# ESP32_with_USBC.net
KiCad netlist of a schematic drawn in Altium Designer
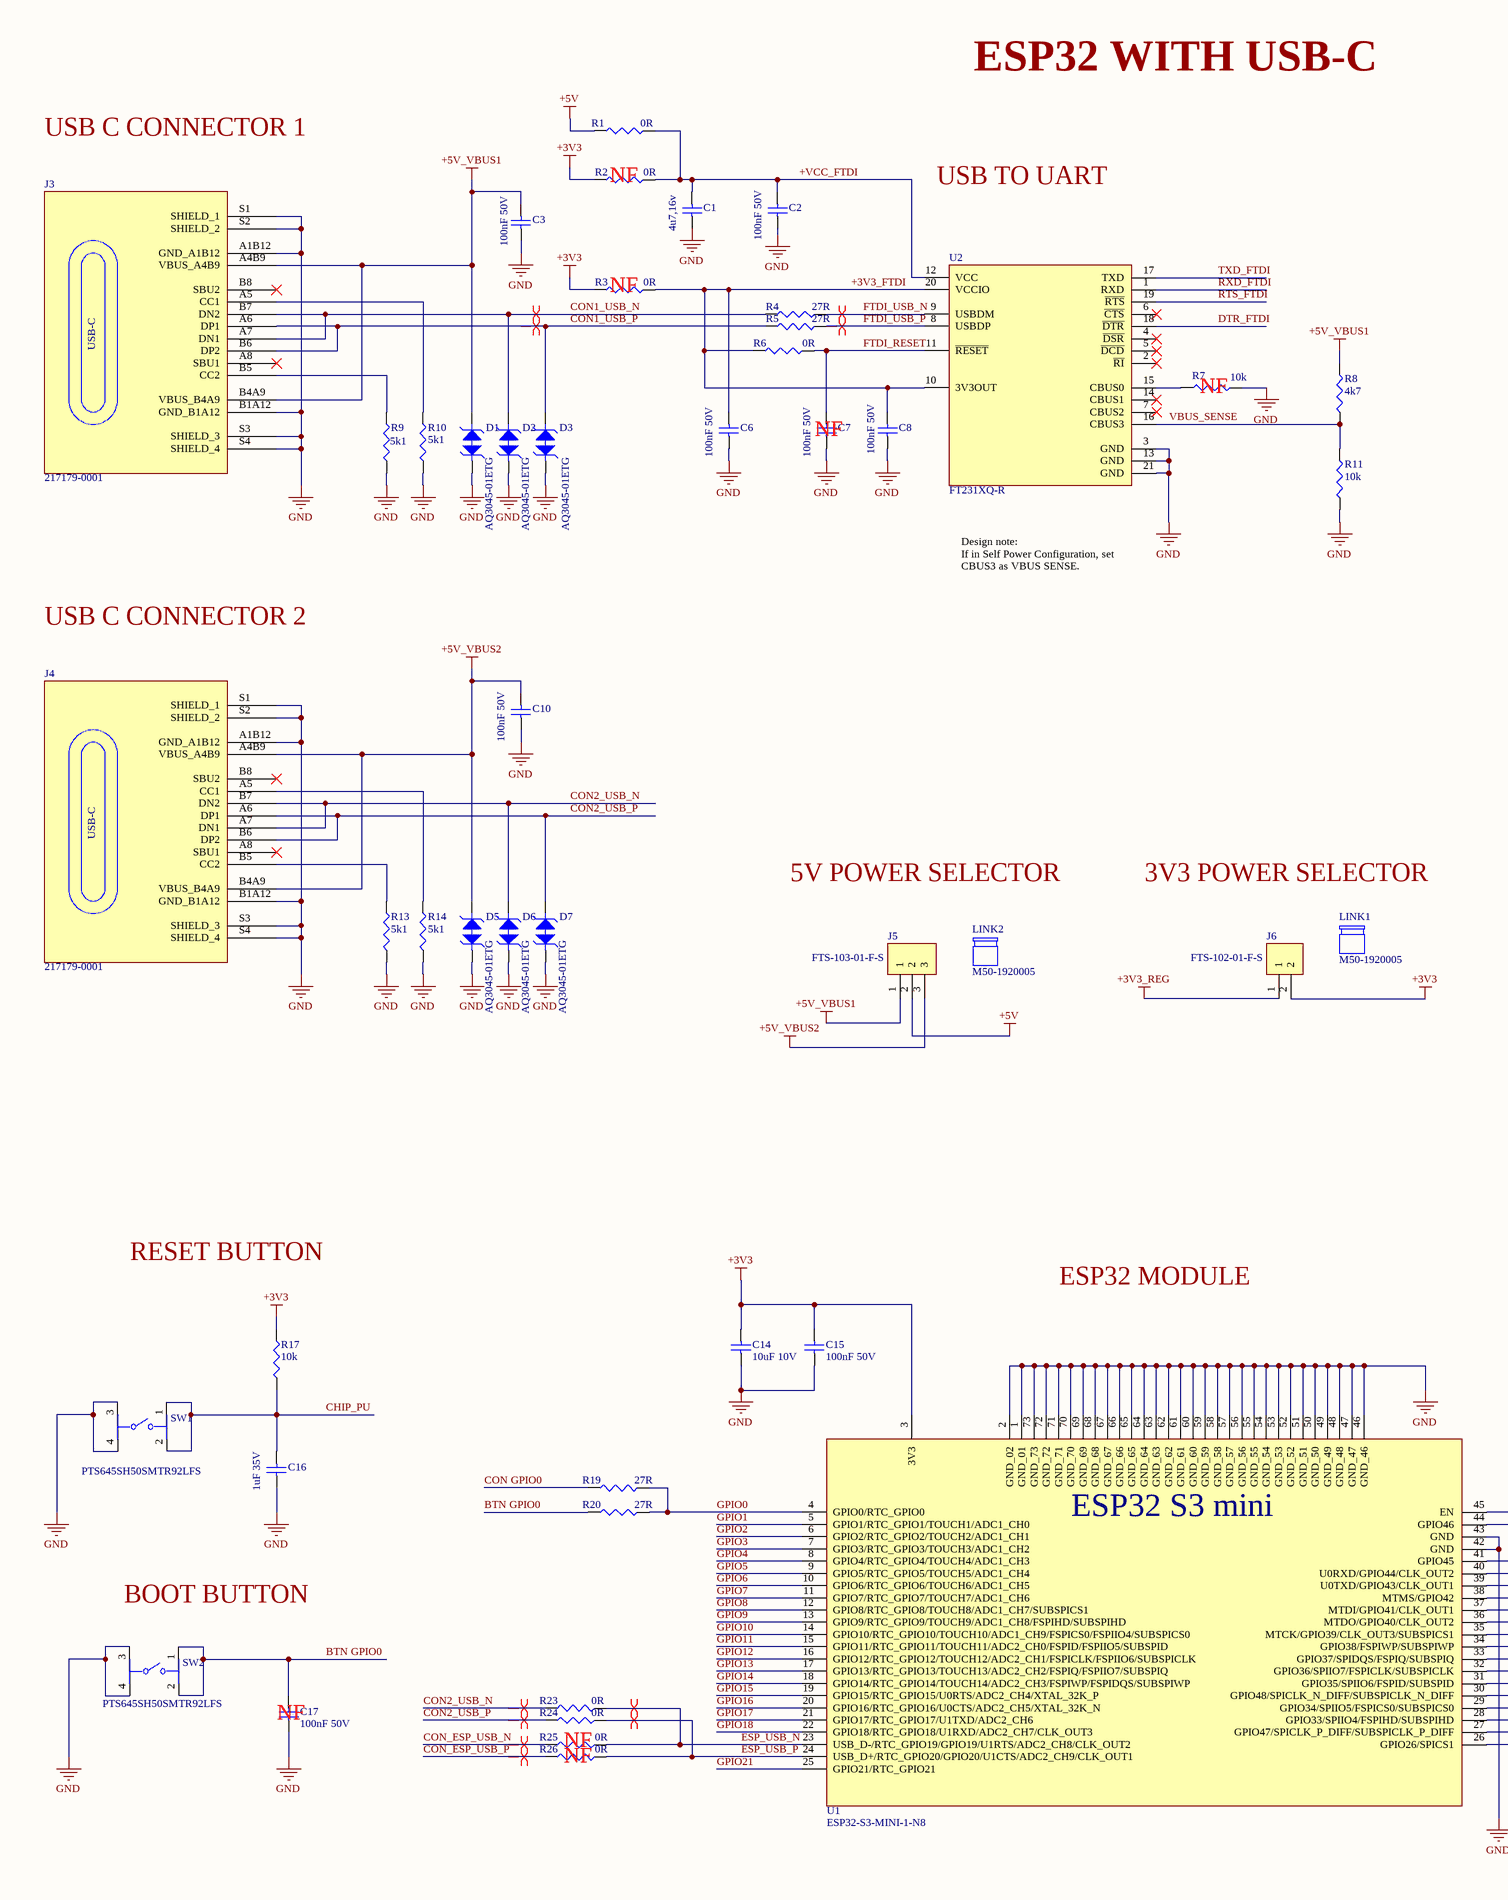
[diagram p0: ESP32 with USBC.SchDoc, left]
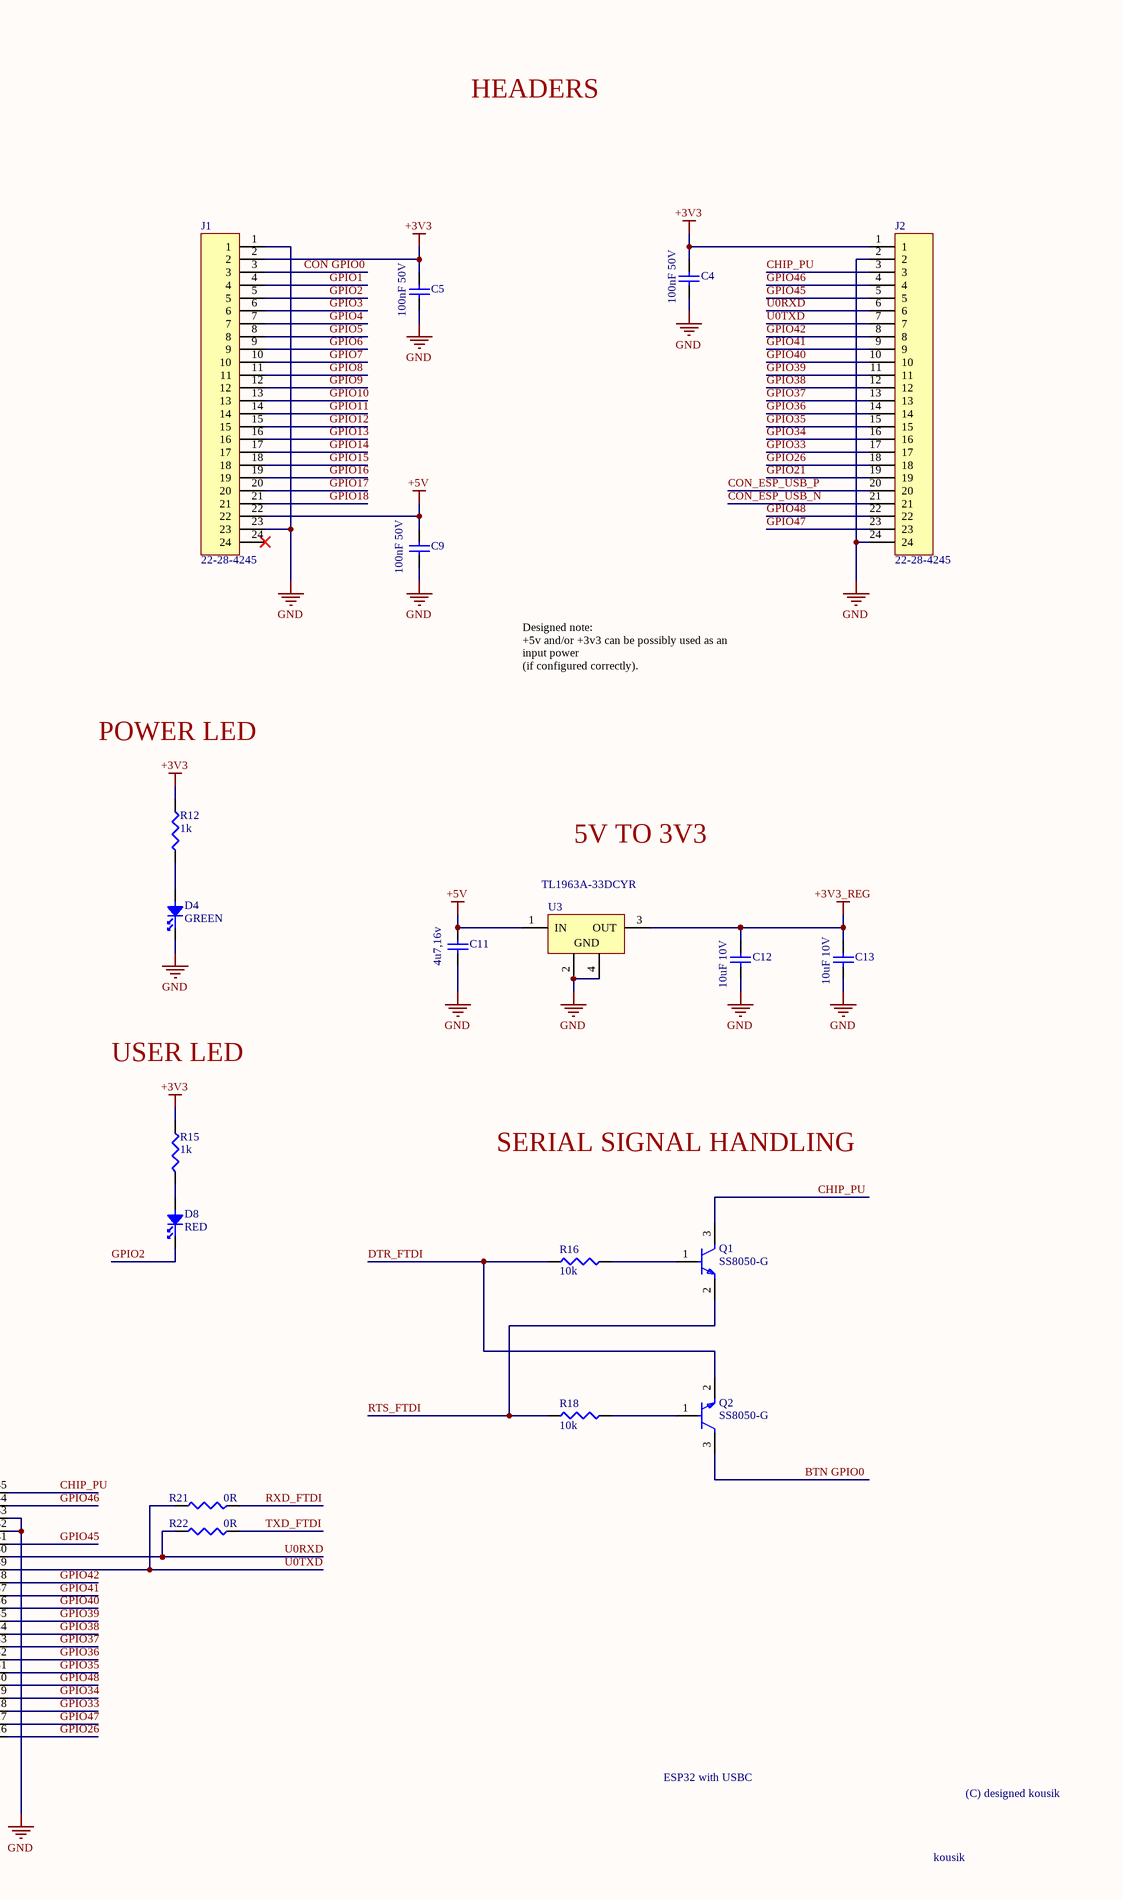
[diagram p1: ESP32 with USBC.SchDoc, right]

(export (version "E")
  (design (tool "Eeschema 10.0.6"))
  (components
    (comp (ref "C1")
      (value "4u7,16v")
      (footprint "CAPC1005X65N")
      (description "CAP CER 4.7UF 16V X5R 0402")
      (fields
        (field (name "MANUFACTURER") "Samsung Electro-Mechanics")
        (field (name "MANUFACTURER PART NUMBER") "CL05A475MO5NUNC")
      )
      (libsource (lib "Schlib") (part "CL05A475MO5NUNC"))
    )
    (comp (ref "C2")
      (value "100nF 50V")
      (footprint "CAPC1005X65N")
      (description "CAP CER 0.1UF 50V X7R 0402")
      (fields
        (field (name "MANUFACTURER") "Samsung Electro-Mechanics")
        (field (name "MANUFACTURER PART NUMBER") "CL05B104KB54PNC")
      )
      (libsource (lib "Schlib") (part "CL05B104KB54PNC"))
    )
    (comp (ref "C3")
      (value "100nF 50V")
      (footprint "CAPC1005X65N")
      (description "CAP CER 0.1UF 50V X7R 0402")
      (fields
        (field (name "MANUFACTURER") "Samsung Electro-Mechanics")
        (field (name "MANUFACTURER PART NUMBER") "CL05B104KB54PNC")
      )
      (libsource (lib "Schlib") (part "CL05B104KB54PNC"))
    )
    (comp (ref "C4")
      (value "100nF 50V")
      (footprint "CAPC1005X65N")
      (description "CAP CER 0.1UF 50V X7R 0402")
      (fields
        (field (name "MANUFACTURER") "Samsung Electro-Mechanics")
        (field (name "MANUFACTURER PART NUMBER") "CL05B104KB54PNC")
      )
      (libsource (lib "Schlib") (part "CL05B104KB54PNC"))
    )
    (comp (ref "C5")
      (value "100nF 50V")
      (footprint "CAPC1005X65N")
      (description "CAP CER 0.1UF 50V X7R 0402")
      (fields
        (field (name "MANUFACTURER") "Samsung Electro-Mechanics")
        (field (name "MANUFACTURER PART NUMBER") "CL05B104KB54PNC")
      )
      (libsource (lib "Schlib") (part "CL05B104KB54PNC"))
    )
    (comp (ref "C6")
      (value "100nF 50V")
      (footprint "CAPC1005X65N")
      (description "CAP CER 0.1UF 50V X7R 0402")
      (fields
        (field (name "MANUFACTURER") "Samsung Electro-Mechanics")
        (field (name "MANUFACTURER PART NUMBER") "CL05B104KB54PNC")
      )
      (libsource (lib "Schlib") (part "CL05B104KB54PNC"))
    )
    (comp (ref "C7")
      (value "100nF 50V")
      (footprint "CAPC1005X65N")
      (description "CAP CER 0.1UF 50V X7R 0402")
      (fields
        (field (name "MANUFACTURER") "Samsung Electro-Mechanics")
        (field (name "MANUFACTURER PART NUMBER") "CL05B104KB54PNC")
      )
      (libsource (lib "Schlib") (part "CL05B104KB54PNC"))
    )
    (comp (ref "C8")
      (value "100nF 50V")
      (footprint "CAPC1005X65N")
      (description "CAP CER 0.1UF 50V X7R 0402")
      (fields
        (field (name "MANUFACTURER") "Samsung Electro-Mechanics")
        (field (name "MANUFACTURER PART NUMBER") "CL05B104KB54PNC")
      )
      (libsource (lib "Schlib") (part "CL05B104KB54PNC"))
    )
    (comp (ref "C9")
      (value "100nF 50V")
      (footprint "CAPC1005X65N")
      (description "CAP CER 0.1UF 50V X7R 0402")
      (fields
        (field (name "MANUFACTURER") "Samsung Electro-Mechanics")
        (field (name "MANUFACTURER PART NUMBER") "CL05B104KB54PNC")
      )
      (libsource (lib "Schlib") (part "CL05B104KB54PNC"))
    )
    (comp (ref "C10")
      (value "100nF 50V")
      (footprint "CAPC1005X65N")
      (description "CAP CER 0.1UF 50V X7R 0402")
      (fields
        (field (name "MANUFACTURER") "Samsung Electro-Mechanics")
        (field (name "MANUFACTURER PART NUMBER") "CL05B104KB54PNC")
      )
      (libsource (lib "Schlib") (part "CL05B104KB54PNC"))
    )
    (comp (ref "C11")
      (value "4u7,16v")
      (footprint "CAPC1005X65N")
      (description "CAP CER 4.7UF 16V X5R 0402")
      (fields
        (field (name "MANUFACTURER") "Samsung Electro-Mechanics")
        (field (name "MANUFACTURER PART NUMBER") "CL05A475MO5NUNC")
      )
      (libsource (lib "Schlib") (part "CL05A475MO5NUNC"))
    )
    (comp (ref "C12")
      (value "10uF 10V")
      (footprint "CAPC1005X65N")
      (description "CAP CER 10UF 10V X5R 0402")
      (fields
        (field (name "MANUFACTURER") "Samsung Electro-Mechanics")
        (field (name "MANUFACTURER PART NUMBER") "CL05A106MP8NUB8")
      )
      (libsource (lib "Schlib") (part "CL05A106MP8NUB8"))
    )
    (comp (ref "C13")
      (value "10uF 10V")
      (footprint "CAPC1005X65N")
      (description "CAP CER 10UF 10V X5R 0402")
      (fields
        (field (name "MANUFACTURER") "Samsung Electro-Mechanics")
        (field (name "MANUFACTURER PART NUMBER") "CL05A106MP8NUB8")
      )
      (libsource (lib "Schlib") (part "CL05A106MP8NUB8"))
    )
    (comp (ref "C14")
      (value "10uF 10V")
      (footprint "CAPC1005X65N")
      (description "CAP CER 10UF 10V X5R 0402")
      (fields
        (field (name "MANUFACTURER") "Samsung Electro-Mechanics")
        (field (name "MANUFACTURER PART NUMBER") "CL05A106MP8NUB8")
      )
      (libsource (lib "Schlib") (part "CL05A106MP8NUB8"))
    )
    (comp (ref "C15")
      (value "100nF 50V")
      (footprint "CAPC1005X65N")
      (description "CAP CER 0.1UF 50V X7R 0402")
      (fields
        (field (name "MANUFACTURER") "Samsung Electro-Mechanics")
        (field (name "MANUFACTURER PART NUMBER") "CL05B104KB54PNC")
      )
      (libsource (lib "Schlib") (part "CL05B104KB54PNC"))
    )
    (comp (ref "C16")
      (value "1uF 35V")
      (footprint "CAPC1005X65N")
      (description "CAP CER 1UF 35V X5R 0402")
      (fields
        (field (name "MANUFACTURER") "Samsung Electro-Mechanics")
        (field (name "MANUFACTURER PART NUMBER") "CL05A105KL5NRNC")
      )
      (libsource (lib "Schlib") (part "CL05A105KL5NRNC"))
    )
    (comp (ref "C17")
      (value "100nF 50V")
      (footprint "CAPC1005X65N")
      (description "CAP CER 0.1UF 50V X7R 0402")
      (fields
        (field (name "MANUFACTURER") "Samsung Electro-Mechanics")
        (field (name "MANUFACTURER PART NUMBER") "CL05B104KB54PNC")
      )
      (libsource (lib "Schlib") (part "CL05B104KB54PNC"))
    )
    (comp (ref "D1")
      (value "AQ3045-01ETG")
      (footprint "SOD882")
      (description "TVS DIODE 5.3VWM 12VC SOD882")
      (fields (field (name "MANUFACTURER") "Littelfuse") (field (name "LCSC PART NUMBER") "C3710326"))
      (libsource (lib "Schlib") (part "AQ3045-01ETG"))
    )
    (comp (ref "D2")
      (value "AQ3045-01ETG")
      (footprint "SOD882")
      (description "TVS DIODE 5.3VWM 12VC SOD882")
      (fields (field (name "MANUFACTURER") "Littelfuse") (field (name "LCSC PART NUMBER") "C3710326"))
      (libsource (lib "Schlib") (part "AQ3045-01ETG"))
    )
    (comp (ref "D3")
      (value "AQ3045-01ETG")
      (footprint "SOD882")
      (description "TVS DIODE 5.3VWM 12VC SOD882")
      (fields (field (name "MANUFACTURER") "Littelfuse") (field (name "LCSC PART NUMBER") "C3710326"))
      (libsource (lib "Schlib") (part "AQ3045-01ETG"))
    )
    (comp (ref "D4")
      (value "GREEN")
      (footprint "LED0402G")
      (description "LED YLW-GRN 0402 SMD")
      (fields
        (field (name "MANUFACTURER") "Vishay")
        (field (name "MANUFACTURER PART NUMBER") "VLMG1500-GS08")
      )
      (libsource (lib "Schlib") (part "VLMG1500-GS08"))
    )
    (comp (ref "D5")
      (value "AQ3045-01ETG")
      (footprint "SOD882")
      (description "TVS DIODE 5.3VWM 12VC SOD882")
      (fields (field (name "MANUFACTURER") "Littelfuse") (field (name "LCSC PART NUMBER") "C3710326"))
      (libsource (lib "Schlib") (part "AQ3045-01ETG"))
    )
    (comp (ref "D6")
      (value "AQ3045-01ETG")
      (footprint "SOD882")
      (description "TVS DIODE 5.3VWM 12VC SOD882")
      (fields (field (name "MANUFACTURER") "Littelfuse") (field (name "LCSC PART NUMBER") "C3710326"))
      (libsource (lib "Schlib") (part "AQ3045-01ETG"))
    )
    (comp (ref "D7")
      (value "AQ3045-01ETG")
      (footprint "SOD882")
      (description "TVS DIODE 5.3VWM 12VC SOD882")
      (fields (field (name "MANUFACTURER") "Littelfuse") (field (name "LCSC PART NUMBER") "C3710326"))
      (libsource (lib "Schlib") (part "AQ3045-01ETG"))
    )
    (comp (ref "D8")
      (value "RED")
      (footprint "LED0402R")
      (description "LED RED 0402 SMD")
      (fields
        (field (name "MANUFACTURER") "Vishay")
        (field (name "MANUFACTURER PART NUMBER") "VLMS1500-GS08")
      )
      (libsource (lib "Schlib") (part "VLMS1500-GS08"))
    )
    (comp (ref "J1")
      (value "22-28-4245")
      (footprint "HDR_1X24_2.54MM")
      (description "CONN HEADER VERT 24POS 2.54MM")
      (fields (field (name "MANUFACTURER") "Molex") (field (name "LCSC PART NUMBER") "C7145888"))
      (libsource (lib "Schlib") (part "22-28-4245"))
    )
    (comp (ref "J2")
      (value "22-28-4245")
      (footprint "HDR_1X24_2.54MM")
      (description "CONN HEADER VERT 24POS 2.54MM")
      (fields (field (name "MANUFACTURER") "Molex") (field (name "LCSC PART NUMBER") "C7145888"))
      (libsource (lib "") (part "22-28-4245_1"))
    )
    (comp (ref "J3")
      (value "217179-0001")
      (footprint "FP-2171790001-MFG")
      (description "CONN RCP USB2.0 TYP C 24P SMD RA")
      (fields (field (name "MANUFACTURER") "Molex") (field (name "LCSC PART NUMBER") "C3197684"))
      (libsource (lib "Schlib") (part "217179-0001"))
    )
    (comp (ref "J4")
      (value "217179-0001")
      (footprint "FP-2171790001-MFG")
      (description "CONN RCP USB2.0 TYP C 24P SMD RA")
      (fields (field (name "MANUFACTURER") "Molex") (field (name "LCSC PART NUMBER") "C3197684"))
      (libsource (lib "Schlib") (part "217179-0001"))
    )
    (comp (ref "J5")
      (value "FTS-103-01-F-S")
      (footprint "HDR_1X3_1.27MM")
      (description "CONN HEADER VERT 3POS 1.27MM")
      (fields (field (name "MANUFACTURER") "Samtec") (field (name "LCSC PART NUMBER") "C3333578"))
      (libsource (lib "Schlib") (part "FTS-103-01-F-S"))
    )
    (comp (ref "J6")
      (value "FTS-102-01-F-S")
      (footprint "HDR_1X2_1.27MM")
      (description "CONN HEADER VERT 2POS 1.27MM")
      (fields (field (name "MANUFACTURER") "Samtec") (field (name "LCSC PART NUMBER") "C6045317"))
      (libsource (lib "Schlib") (part "FTS-102-01-F-S"))
    )
    (comp (ref "LINK1")
      (value "M50-1920005")
      (description "CONN SHUNT 1.27MM RED")
      (fields (field (name "MANUFACTURER") "Harwin") (field (name "LCSC PART NUMBER") "C6985646"))
      (libsource (lib "Schlib") (part "M50-1920005"))
    )
    (comp (ref "LINK2")
      (value "M50-1920005")
      (description "CONN SHUNT 1.27MM RED")
      (fields (field (name "MANUFACTURER") "Harwin") (field (name "LCSC PART NUMBER") "C6985646"))
      (libsource (lib "Schlib") (part "M50-1920005"))
    )
    (comp (ref "Q1")
      (value "SS8050-G")
      (footprint "FP-SS8050-G-IPC_B")
      (description "TRANS NPN 25V 1.5A SOT-23-3")
      (fields (field (name "MANUFACTURER") "Comchip") (field (name "LCSC PART NUMBER") "C164886"))
      (libsource (lib "Schlib") (part "SS8050-G"))
    )
    (comp (ref "Q2")
      (value "SS8050-G")
      (footprint "FP-SS8050-G-IPC_B")
      (description "TRANS NPN 25V 1.5A SOT-23-3")
      (fields (field (name "MANUFACTURER") "Comchip") (field (name "LCSC PART NUMBER") "C164886"))
      (libsource (lib "Schlib") (part "SS8050-G"))
    )
    (comp (ref "R1")
      (value "0R")
      (footprint "RESC1005X37N")
      (description "RES 0 OHM JUMPER 1/16W 0402")
      (fields
        (field (name "MANUFACTURER") "Yageo Group")
        (field (name "MANUFACTURER PART NUMBER") "RC0402JR-070RL")
      )
      (libsource (lib "Schlib") (part "RC0402JR-070RL"))
    )
    (comp (ref "R2")
      (value "0R")
      (footprint "RESC1005X37N")
      (description "RES 0 OHM JUMPER 1/16W 0402")
      (fields
        (field (name "MANUFACTURER") "Yageo Group")
        (field (name "MANUFACTURER PART NUMBER") "RC0402JR-070RL")
      )
      (libsource (lib "Schlib") (part "RC0402JR-070RL"))
    )
    (comp (ref "R3")
      (value "0R")
      (footprint "RESC1005X37N")
      (description "RES 0 OHM JUMPER 1/16W 0402")
      (fields
        (field (name "MANUFACTURER") "Yageo Group")
        (field (name "MANUFACTURER PART NUMBER") "RC0402JR-070RL")
      )
      (libsource (lib "Schlib") (part "RC0402JR-070RL"))
    )
    (comp (ref "R4")
      (value "27R")
      (footprint "RESC1005X37N")
      (description "RES 27 OHM 1% 1/16W 0402")
      (fields
        (field (name "MANUFACTURER") "Yageo Group")
        (field (name "MANUFACTURER PART NUMBER") "RC0402FR-0727RL")
      )
      (libsource (lib "Schlib") (part "RC0402FR-0727RL"))
    )
    (comp (ref "R5")
      (value "27R")
      (footprint "RESC1005X37N")
      (description "RES 27 OHM 1% 1/16W 0402")
      (fields
        (field (name "MANUFACTURER") "Yageo Group")
        (field (name "MANUFACTURER PART NUMBER") "RC0402FR-0727RL")
      )
      (libsource (lib "Schlib") (part "RC0402FR-0727RL"))
    )
    (comp (ref "R6")
      (value "0R")
      (footprint "RESC1005X37N")
      (description "RES 0 OHM JUMPER 1/16W 0402")
      (fields
        (field (name "MANUFACTURER") "Yageo Group")
        (field (name "MANUFACTURER PART NUMBER") "RC0402JR-070RL")
      )
      (libsource (lib "Schlib") (part "RC0402JR-070RL"))
    )
    (comp (ref "R7")
      (value "10k")
      (footprint "RESC1005X37N")
      (description "RES SMD 10K OHM 1% 1/16W 0402")
      (fields
        (field (name "MANUFACTURER") "Yageo Group")
        (field (name "MANUFACTURER PART NUMBER") "AC0402FR-0710KL")
      )
      (libsource (lib "Schlib") (part "AC0402FR-0710KL"))
    )
    (comp (ref "R8")
      (value "4k7")
      (footprint "RESC1005X37N")
      (description "RES 4.7K OHM 1% 1/16W 0402")
      (fields
        (field (name "MANUFACTURER") "Yageo Group")
        (field (name "MANUFACTURER PART NUMBER") "RC0402FR-074K7L")
      )
      (libsource (lib "Schlib") (part "RC0402FR-074K7L"))
    )
    (comp (ref "R9")
      (value "5k1")
      (footprint "RESC1005X37N")
      (description "RES SMD 5.1K OHM 1% 1/16W 0402")
      (fields
        (field (name "MANUFACTURER") "Yageo Group")
        (field (name "MANUFACTURER PART NUMBER") "AC0402FR-075K1L")
      )
      (libsource (lib "Schlib") (part "AC0402FR-075K1L"))
    )
    (comp (ref "R10")
      (value "5k1")
      (footprint "RESC1005X37N")
      (description "RES SMD 5.1K OHM 1% 1/16W 0402")
      (fields
        (field (name "MANUFACTURER") "Yageo Group")
        (field (name "MANUFACTURER PART NUMBER") "AC0402FR-075K1L")
      )
      (libsource (lib "Schlib") (part "AC0402FR-075K1L"))
    )
    (comp (ref "R11")
      (value "10k")
      (footprint "RESC1005X37N")
      (description "RES SMD 10K OHM 1% 1/16W 0402")
      (fields
        (field (name "MANUFACTURER") "Yageo Group")
        (field (name "MANUFACTURER PART NUMBER") "AC0402FR-0710KL")
      )
      (libsource (lib "Schlib") (part "AC0402FR-0710KL"))
    )
    (comp (ref "R12")
      (value "1k")
      (footprint "RESC1005X37N")
      (description "RES 1K OHM 1% 1/16W 0402")
      (fields
        (field (name "MANUFACTURER") "Yageo Group")
        (field (name "MANUFACTURER PART NUMBER") "RC0402FR-071KL")
      )
      (libsource (lib "Schlib") (part "RC0402FR-071KL"))
    )
    (comp (ref "R13")
      (value "5k1")
      (footprint "RESC1005X37N")
      (description "RES SMD 5.1K OHM 1% 1/16W 0402")
      (fields
        (field (name "MANUFACTURER") "Yageo Group")
        (field (name "MANUFACTURER PART NUMBER") "AC0402FR-075K1L")
      )
      (libsource (lib "Schlib") (part "AC0402FR-075K1L"))
    )
    (comp (ref "R14")
      (value "5k1")
      (footprint "RESC1005X37N")
      (description "RES SMD 5.1K OHM 1% 1/16W 0402")
      (fields
        (field (name "MANUFACTURER") "Yageo Group")
        (field (name "MANUFACTURER PART NUMBER") "AC0402FR-075K1L")
      )
      (libsource (lib "Schlib") (part "AC0402FR-075K1L"))
    )
    (comp (ref "R15")
      (value "1k")
      (footprint "RESC1005X37N")
      (description "RES 1K OHM 1% 1/16W 0402")
      (fields
        (field (name "MANUFACTURER") "Yageo Group")
        (field (name "MANUFACTURER PART NUMBER") "RC0402FR-071KL")
      )
      (libsource (lib "Schlib") (part "RC0402FR-071KL"))
    )
    (comp (ref "R16")
      (value "10k")
      (footprint "RESC1005X37N")
      (description "RES SMD 10K OHM 1% 1/16W 0402")
      (fields
        (field (name "MANUFACTURER") "Yageo Group")
        (field (name "MANUFACTURER PART NUMBER") "AC0402FR-0710KL")
      )
      (libsource (lib "Schlib") (part "AC0402FR-0710KL"))
    )
    (comp (ref "R17")
      (value "10k")
      (footprint "RESC1005X37N")
      (description "RES SMD 10K OHM 1% 1/16W 0402")
      (fields
        (field (name "MANUFACTURER") "Yageo Group")
        (field (name "MANUFACTURER PART NUMBER") "AC0402FR-0710KL")
      )
      (libsource (lib "Schlib") (part "AC0402FR-0710KL"))
    )
    (comp (ref "R18")
      (value "10k")
      (footprint "RESC1005X37N")
      (description "RES SMD 10K OHM 1% 1/16W 0402")
      (fields
        (field (name "MANUFACTURER") "Yageo Group")
        (field (name "MANUFACTURER PART NUMBER") "AC0402FR-0710KL")
      )
      (libsource (lib "Schlib") (part "AC0402FR-0710KL"))
    )
    (comp (ref "R19")
      (value "27R")
      (footprint "RESC1005X37N")
      (description "RES 27 OHM 1% 1/16W 0402")
      (fields
        (field (name "MANUFACTURER") "Yageo Group")
        (field (name "MANUFACTURER PART NUMBER") "RC0402FR-0727RL")
      )
      (libsource (lib "Schlib") (part "RC0402FR-0727RL"))
    )
    (comp (ref "R20")
      (value "27R")
      (footprint "RESC1005X37N")
      (description "RES 27 OHM 1% 1/16W 0402")
      (fields
        (field (name "MANUFACTURER") "Yageo Group")
        (field (name "MANUFACTURER PART NUMBER") "RC0402FR-0727RL")
      )
      (libsource (lib "Schlib") (part "RC0402FR-0727RL"))
    )
    (comp (ref "R21")
      (value "0R")
      (footprint "RESC1005X37N")
      (description "RES 0 OHM JUMPER 1/16W 0402")
      (fields
        (field (name "MANUFACTURER") "Yageo Group")
        (field (name "MANUFACTURER PART NUMBER") "RC0402JR-070RL")
      )
      (libsource (lib "Schlib") (part "RC0402JR-070RL"))
    )
    (comp (ref "R22")
      (value "0R")
      (footprint "RESC1005X37N")
      (description "RES 0 OHM JUMPER 1/16W 0402")
      (fields
        (field (name "MANUFACTURER") "Yageo Group")
        (field (name "MANUFACTURER PART NUMBER") "RC0402JR-070RL")
      )
      (libsource (lib "Schlib") (part "RC0402JR-070RL"))
    )
    (comp (ref "R23")
      (value "0R")
      (footprint "RESC1005X37N")
      (description "RES 0 OHM JUMPER 1/16W 0402")
      (fields
        (field (name "MANUFACTURER") "Yageo Group")
        (field (name "MANUFACTURER PART NUMBER") "RC0402JR-070RL")
      )
      (libsource (lib "Schlib") (part "RC0402JR-070RL"))
    )
    (comp (ref "R24")
      (value "0R")
      (footprint "RESC1005X37N")
      (description "RES 0 OHM JUMPER 1/16W 0402")
      (fields
        (field (name "MANUFACTURER") "Yageo Group")
        (field (name "MANUFACTURER PART NUMBER") "RC0402JR-070RL")
      )
      (libsource (lib "Schlib") (part "RC0402JR-070RL"))
    )
    (comp (ref "R25")
      (value "0R")
      (footprint "RESC1005X37N")
      (description "RES 0 OHM JUMPER 1/16W 0402")
      (fields
        (field (name "MANUFACTURER") "Yageo Group")
        (field (name "MANUFACTURER PART NUMBER") "RC0402JR-070RL")
      )
      (libsource (lib "Schlib") (part "RC0402JR-070RL"))
    )
    (comp (ref "R26")
      (value "0R")
      (footprint "RESC1005X37N")
      (description "RES 0 OHM JUMPER 1/16W 0402")
      (fields
        (field (name "MANUFACTURER") "Yageo Group")
        (field (name "MANUFACTURER PART NUMBER") "RC0402JR-070RL")
      )
      (libsource (lib "Schlib") (part "RC0402JR-070RL"))
    )
    (comp (ref "SW1")
      (value "PTS645SH50SMTR92LFS")
      (footprint "FP-PTS645SH50SMTR92LFS-MFG")
      (description "SWITCH TACTILE SPST-NO 0.05A 12V")
      (fields (field (name "MANUFACTURER") "C&K Components") (field (name "LCSC PART NUMBER") "C221869"))
      (libsource (lib "Schlib") (part "PTS645SH50SMTR92LFS"))
    )
    (comp (ref "SW2")
      (value "PTS645SH50SMTR92LFS")
      (footprint "FP-PTS645SH50SMTR92LFS-MFG")
      (description "SWITCH TACTILE SPST-NO 0.05A 12V")
      (fields (field (name "MANUFACTURER") "C&K Components") (field (name "LCSC PART NUMBER") "C221869"))
      (libsource (lib "Schlib") (part "PTS645SH50SMTR92LFS"))
    )
    (comp (ref "U1")
      (value "ESP32-S3-MINI-1-N8")
      (footprint "XCVR_ESP32-S3-MINI-1-N8")
      (description "20.5dBm ESP32-S3FN8 Chip 2.4GHz SMD WiFi Modules ROHS")
      (fields (field (name "MANUFACTURER") "Espressif Systems") (field (name "LCSC PART NUMBER") "C2913206"))
      (libsource (lib "Schlib") (part "ESP32-S3-MINI-1-N8"))
    )
    (comp (ref "U2")
      (value "FT231XQ-R")
      (footprint "FP-QFN-20-IPC_B")
      (description "IC USB SERIAL FULL UART 20QFN")
      (fields (field (name "MANUFACTURER") "FTDI") (field (name "LCSC PART NUMBER") "C132159"))
      (libsource (lib "Schlib") (part "FT231XQ-R"))
    )
    (comp (ref "U3")
      (value "TL1963A-33DCYR")
      (footprint "DCY0004A_N")
      (description "IC REG LIN 3.3V 1.5A SOT-223-4")
      (fields (field (name "MANUFACTURER") "Texas Instruments") (field (name "LCSC PART NUMBER") "C181262"))
      (libsource (lib "Schlib") (part "TL1963A-33DCYR"))
    )
  )
  (nets
    (net (code "1") (name "+3V3") (class "Default")
      (node (ref "C14") (pin "2") (pinfunction "2_2") (pintype "passive"))
      (node (ref "C15") (pin "2") (pinfunction "2_2") (pintype "passive"))
      (node (ref "C4") (pin "2") (pinfunction "2_2") (pintype "passive"))
      (node (ref "C5") (pin "2") (pinfunction "2_2") (pintype "passive"))
      (node (ref "J1") (pin "2") (pinfunction "2_2") (pintype "passive"))
      (node (ref "J2") (pin "1") (pinfunction "1_1") (pintype "passive"))
      (node (ref "J6") (pin "2") (pinfunction "2_2") (pintype "passive"))
      (node (ref "R12") (pin "2") (pinfunction "2_2") (pintype "passive"))
      (node (ref "R15") (pin "2") (pinfunction "2_2") (pintype "passive"))
      (node (ref "R17") (pin "2") (pinfunction "2_2") (pintype "passive"))
      (node (ref "R2") (pin "1") (pinfunction "1_1") (pintype "passive"))
      (node (ref "R3") (pin "1") (pinfunction "1_1") (pintype "passive"))
      (node (ref "U1") (pin "3") (pinfunction "3V3_3") (pintype "passive"))
    )
    (net (code "2") (name "+3V3_REG") (class "Default")
      (node (ref "C12") (pin "2") (pinfunction "2_2") (pintype "passive"))
      (node (ref "C13") (pin "2") (pinfunction "2_2") (pintype "passive"))
      (node (ref "J6") (pin "1") (pinfunction "1_1") (pintype "passive"))
      (node (ref "U3") (pin "3") (pinfunction "OUT_3") (pintype "power_in"))
    )
    (net (code "3") (name "+5V") (class "Default")
      (node (ref "C11") (pin "2") (pinfunction "2_2") (pintype "passive"))
      (node (ref "C9") (pin "2") (pinfunction "2_2") (pintype "passive"))
      (node (ref "J1") (pin "22") (pinfunction "22_22") (pintype "passive"))
      (node (ref "J5") (pin "2") (pinfunction "2_2") (pintype "passive"))
      (node (ref "R1") (pin "1") (pinfunction "1_1") (pintype "passive"))
      (node (ref "U3") (pin "1") (pinfunction "IN_1") (pintype "power_in"))
    )
    (net (code "4") (name "+5V_VBUS1") (class "Default")
      (node (ref "C3") (pin "2") (pinfunction "2_2") (pintype "passive"))
      (node (ref "D1") (pin "2") (pinfunction "2_2") (pintype "passive"))
      (node (ref "J3") (pin "A4B9") (pinfunction "VBUS_A4B9_A4B9") (pintype "passive"))
      (node (ref "J3") (pin "B4A9") (pinfunction "VBUS_B4A9_B4A9") (pintype "passive"))
      (node (ref "J5") (pin "1") (pinfunction "1_1") (pintype "passive"))
      (node (ref "R8") (pin "2") (pinfunction "2_2") (pintype "passive"))
    )
    (net (code "5") (name "+5V_VBUS2") (class "Default")
      (node (ref "C10") (pin "2") (pinfunction "2_2") (pintype "passive"))
      (node (ref "D5") (pin "2") (pinfunction "2_2") (pintype "passive"))
      (node (ref "J4") (pin "A4B9") (pinfunction "VBUS_A4B9_A4B9") (pintype "passive"))
      (node (ref "J4") (pin "B4A9") (pinfunction "VBUS_B4A9_B4A9") (pintype "passive"))
      (node (ref "J5") (pin "3") (pinfunction "3_3") (pintype "passive"))
    )
    (net (code "6") (name "/+3V3_FTDI") (class "Default")
      (node (ref "C6") (pin "2") (pinfunction "2_2") (pintype "passive"))
      (node (ref "C8") (pin "2") (pinfunction "2_2") (pintype "passive"))
      (node (ref "R3") (pin "2") (pinfunction "2_2") (pintype "passive"))
      (node (ref "R6") (pin "1") (pinfunction "1_1") (pintype "passive"))
      (node (ref "U2") (pin "10") (pinfunction "3V3OUT_10") (pintype "passive"))
      (node (ref "U2") (pin "20") (pinfunction "VCCIO_20") (pintype "passive"))
    )
    (net (code "7") (name "/+VCC_FTDI") (class "Default")
      (node (ref "C1") (pin "2") (pinfunction "2_2") (pintype "passive"))
      (node (ref "C2") (pin "2") (pinfunction "2_2") (pintype "passive"))
      (node (ref "R1") (pin "2") (pinfunction "2_2") (pintype "passive"))
      (node (ref "R2") (pin "2") (pinfunction "2_2") (pintype "passive"))
      (node (ref "U2") (pin "12") (pinfunction "VCC_12") (pintype "passive"))
    )
    (net (code "8") (name "/BTN GPIO0") (class "Default")
      (node (ref "C17") (pin "2") (pinfunction "2_2") (pintype "passive"))
      (node (ref "Q2") (pin "3") (pinfunction "C_3") (pintype "passive"))
      (node (ref "R20") (pin "1") (pinfunction "1_1") (pintype "passive"))
      (node (ref "SW2") (pin "1") (pinfunction "1_1") (pintype "passive"))
      (node (ref "SW2") (pin "2") (pinfunction "2_2") (pintype "passive"))
    )
    (net (code "9") (name "/CHIP_PU") (class "Default")
      (node (ref "C16") (pin "2") (pinfunction "2_2") (pintype "passive"))
      (node (ref "J2") (pin "3") (pinfunction "3_3") (pintype "passive"))
      (node (ref "Q1") (pin "3") (pinfunction "C_3") (pintype "passive"))
      (node (ref "R17") (pin "1") (pinfunction "1_1") (pintype "passive"))
      (node (ref "SW1") (pin "1") (pinfunction "1_1") (pintype "passive"))
      (node (ref "SW1") (pin "2") (pinfunction "2_2") (pintype "passive"))
      (node (ref "U1") (pin "45") (pinfunction "EN_45") (pintype "passive"))
    )
    (net (code "10") (name "/CON GPIO0") (class "Default")
      (node (ref "J1") (pin "3") (pinfunction "3_3") (pintype "passive"))
      (node (ref "R19") (pin "1") (pinfunction "1_1") (pintype "passive"))
    )
    (net (code "11") (name "/CON1_USB_N") (class "Default")
      (node (ref "D2") (pin "2") (pinfunction "2_2") (pintype "passive"))
      (node (ref "J3") (pin "A7") (pinfunction "DN1_A7") (pintype "passive"))
      (node (ref "J3") (pin "B7") (pinfunction "DN2_B7") (pintype "passive"))
      (node (ref "R4") (pin "1") (pinfunction "1_1") (pintype "passive"))
    )
    (net (code "12") (name "/CON1_USB_P") (class "Default")
      (node (ref "D3") (pin "2") (pinfunction "2_2") (pintype "passive"))
      (node (ref "J3") (pin "A6") (pinfunction "DP1_A6") (pintype "passive"))
      (node (ref "J3") (pin "B6") (pinfunction "DP2_B6") (pintype "passive"))
      (node (ref "R5") (pin "1") (pinfunction "1_1") (pintype "passive"))
    )
    (net (code "13") (name "/CON2_USB_N") (class "Default")
      (node (ref "D6") (pin "2") (pinfunction "2_2") (pintype "passive"))
      (node (ref "J4") (pin "A7") (pinfunction "DN1_A7") (pintype "passive"))
      (node (ref "J4") (pin "B7") (pinfunction "DN2_B7") (pintype "passive"))
      (node (ref "R23") (pin "1") (pinfunction "1_1") (pintype "passive"))
    )
    (net (code "14") (name "/CON2_USB_P") (class "Default")
      (node (ref "D7") (pin "2") (pinfunction "2_2") (pintype "passive"))
      (node (ref "J4") (pin "A6") (pinfunction "DP1_A6") (pintype "passive"))
      (node (ref "J4") (pin "B6") (pinfunction "DP2_B6") (pintype "passive"))
      (node (ref "R24") (pin "1") (pinfunction "1_1") (pintype "passive"))
    )
    (net (code "15") (name "/CON_ESP_USB_N") (class "Default")
      (node (ref "J2") (pin "21") (pinfunction "21_21") (pintype "passive"))
      (node (ref "R25") (pin "1") (pinfunction "1_1") (pintype "passive"))
    )
    (net (code "16") (name "/CON_ESP_USB_P") (class "Default")
      (node (ref "J2") (pin "20") (pinfunction "20_20") (pintype "passive"))
      (node (ref "R26") (pin "1") (pinfunction "1_1") (pintype "passive"))
    )
    (net (code "17") (name "/DTR_FTDI") (class "Default")
      (node (ref "Q2") (pin "2") (pinfunction "E_2") (pintype "passive"))
      (node (ref "R16") (pin "2") (pinfunction "2_2") (pintype "passive"))
      (node (ref "U2") (pin "18") (pinfunction "~{DTR}_18") (pintype "passive"))
    )
    (net (code "18") (name "/ESP_USB_N") (class "Default")
      (node (ref "R23") (pin "2") (pinfunction "2_2") (pintype "passive"))
      (node (ref "R25") (pin "2") (pinfunction "2_2") (pintype "passive"))
      (node (ref "U1") (pin "23") (pinfunction "USB_D-/RTC_GPIO19/GPIO19/U1RTS/ADC2_CH8/CLK_OUT2_23") (pintype "passive"))
    )
    (net (code "19") (name "/ESP_USB_P") (class "Default")
      (node (ref "R24") (pin "2") (pinfunction "2_2") (pintype "passive"))
      (node (ref "R26") (pin "2") (pinfunction "2_2") (pintype "passive"))
      (node (ref "U1") (pin "24") (pinfunction "USB_D+/RTC_GPIO20/GPIO20/U1CTS/ADC2_CH9/CLK_OUT1_24") (pintype "passive"))
    )
    (net (code "20") (name "/FTDI_RESET") (class "Default")
      (node (ref "C7") (pin "2") (pinfunction "2_2") (pintype "passive"))
      (node (ref "R6") (pin "2") (pinfunction "2_2") (pintype "passive"))
      (node (ref "U2") (pin "11") (pinfunction "~{RESET}_11") (pintype "passive"))
    )
    (net (code "21") (name "/FTDI_USB_N") (class "Default")
      (node (ref "R4") (pin "2") (pinfunction "2_2") (pintype "passive"))
      (node (ref "U2") (pin "9") (pinfunction "USBDM_9") (pintype "passive"))
    )
    (net (code "22") (name "/FTDI_USB_P") (class "Default")
      (node (ref "R5") (pin "2") (pinfunction "2_2") (pintype "passive"))
      (node (ref "U2") (pin "8") (pinfunction "USBDP_8") (pintype "passive"))
    )
    (net (code "23") (name "/GPIO0") (class "Default")
      (node (ref "R19") (pin "2") (pinfunction "2_2") (pintype "passive"))
      (node (ref "R20") (pin "2") (pinfunction "2_2") (pintype "passive"))
      (node (ref "U1") (pin "4") (pinfunction "GPIO0/RTC_GPIO0_4") (pintype "passive"))
    )
    (net (code "24") (name "/GPIO1") (class "Default")
      (node (ref "J1") (pin "4") (pinfunction "4_4") (pintype "passive"))
      (node (ref "U1") (pin "5") (pinfunction "GPIO1/RTC_GPIO1/TOUCH1/ADC1_CH0_5") (pintype "passive"))
    )
    (net (code "25") (name "/GPIO2") (class "Default")
      (node (ref "D8") (pin "1") (pinfunction "1_1") (pintype "passive"))
      (node (ref "J1") (pin "5") (pinfunction "5_5") (pintype "passive"))
      (node (ref "U1") (pin "6") (pinfunction "GPIO2/RTC_GPIO2/TOUCH2/ADC1_CH1_6") (pintype "passive"))
    )
    (net (code "26") (name "/GPIO3") (class "Default")
      (node (ref "J1") (pin "6") (pinfunction "6_6") (pintype "passive"))
      (node (ref "U1") (pin "7") (pinfunction "GPIO3/RTC_GPIO3/TOUCH3/ADC1_CH2_7") (pintype "passive"))
    )
    (net (code "27") (name "/GPIO4") (class "Default")
      (node (ref "J1") (pin "7") (pinfunction "7_7") (pintype "passive"))
      (node (ref "U1") (pin "8") (pinfunction "GPIO4/RTC_GPIO4/TOUCH4/ADC1_CH3_8") (pintype "passive"))
    )
    (net (code "28") (name "/GPIO5") (class "Default")
      (node (ref "J1") (pin "8") (pinfunction "8_8") (pintype "passive"))
      (node (ref "U1") (pin "9") (pinfunction "GPIO5/RTC_GPIO5/TOUCH5/ADC1_CH4_9") (pintype "passive"))
    )
    (net (code "29") (name "/GPIO6") (class "Default")
      (node (ref "J1") (pin "9") (pinfunction "9_9") (pintype "passive"))
      (node (ref "U1") (pin "10") (pinfunction "GPIO6/RTC_GPIO6/TOUCH6/ADC1_CH5_10") (pintype "passive"))
    )
    (net (code "30") (name "/GPIO7") (class "Default")
      (node (ref "J1") (pin "10") (pinfunction "10_10") (pintype "passive"))
      (node (ref "U1") (pin "11") (pinfunction "GPIO7/RTC_GPIO7/TOUCH7/ADC1_CH6_11") (pintype "passive"))
    )
    (net (code "31") (name "/GPIO8") (class "Default")
      (node (ref "J1") (pin "11") (pinfunction "11_11") (pintype "passive"))
      (node (ref "U1") (pin "12") (pinfunction "GPIO8/RTC_GPIO8/TOUCH8/ADC1_CH7/SUBSPICS1_12") (pintype "passive"))
    )
    (net (code "32") (name "/GPIO9") (class "Default")
      (node (ref "J1") (pin "12") (pinfunction "12_12") (pintype "passive"))
      (node (ref "U1") (pin "13") (pinfunction "GPIO9/RTC_GPIO9/TOUCH9/ADC1_CH8/FSPIHD/SUBSPIHD_13") (pintype "passive"))
    )
    (net (code "33") (name "/GPIO10") (class "Default")
      (node (ref "J1") (pin "13") (pinfunction "13_13") (pintype "passive"))
      (node (ref "U1") (pin "14") (pinfunction "GPIO10/RTC_GPIO10/TOUCH10/ADC1_CH9/FSPICS0/FSPIIO4/SUBSPICS0_14") (pintype "passive"))
    )
    (net (code "34") (name "/GPIO11") (class "Default")
      (node (ref "J1") (pin "14") (pinfunction "14_14") (pintype "passive"))
      (node (ref "U1") (pin "15") (pinfunction "GPIO11/RTC_GPIO11/TOUCH11/ADC2_CH0/FSPID/FSPIIO5/SUBSPID_15") (pintype "passive"))
    )
    (net (code "35") (name "/GPIO12") (class "Default")
      (node (ref "J1") (pin "15") (pinfunction "15_15") (pintype "passive"))
      (node (ref "U1") (pin "16") (pinfunction "GPIO12/RTC_GPIO12/TOUCH12/ADC2_CH1/FSPICLK/FSPIIO6/SUBSPICLK_16") (pintype "passive"))
    )
    (net (code "36") (name "/GPIO13") (class "Default")
      (node (ref "J1") (pin "16") (pinfunction "16_16") (pintype "passive"))
      (node (ref "U1") (pin "17") (pinfunction "GPIO13/RTC_GPIO13/TOUCH13/ADC2_CH2/FSPIQ/FSPIIO7/SUBSPIQ_17") (pintype "passive"))
    )
    (net (code "37") (name "/GPIO14") (class "Default")
      (node (ref "J1") (pin "17") (pinfunction "17_17") (pintype "passive"))
      (node (ref "U1") (pin "18") (pinfunction "GPIO14/RTC_GPIO14/TOUCH14/ADC2_CH3/FSPIWP/FSPIDQS/SUBSPIWP_18") (pintype "passive"))
    )
    (net (code "38") (name "/GPIO15") (class "Default")
      (node (ref "J1") (pin "18") (pinfunction "18_18") (pintype "passive"))
      (node (ref "U1") (pin "19") (pinfunction "GPIO15/RTC_GPIO15/U0RTS/ADC2_CH4/XTAL_32K_P_19") (pintype "passive"))
    )
    (net (code "39") (name "/GPIO16") (class "Default")
      (node (ref "J1") (pin "19") (pinfunction "19_19") (pintype "passive"))
      (node (ref "U1") (pin "20") (pinfunction "GPIO16/RTC_GPIO16/U0CTS/ADC2_CH5/XTAL_32K_N_20") (pintype "passive"))
    )
    (net (code "40") (name "/GPIO17") (class "Default")
      (node (ref "J1") (pin "20") (pinfunction "20_20") (pintype "passive"))
      (node (ref "U1") (pin "21") (pinfunction "GPIO17/RTC_GPIO17/U1TXD/ADC2_CH6_21") (pintype "passive"))
    )
    (net (code "41") (name "/GPIO18") (class "Default")
      (node (ref "J1") (pin "21") (pinfunction "21_21") (pintype "passive"))
      (node (ref "U1") (pin "22") (pinfunction "GPIO18/RTC_GPIO18/U1RXD/ADC2_CH7/CLK_OUT3_22") (pintype "passive"))
    )
    (net (code "42") (name "/GPIO21") (class "Default")
      (node (ref "J2") (pin "19") (pinfunction "19_19") (pintype "passive"))
      (node (ref "U1") (pin "25") (pinfunction "GPIO21/RTC_GPIO21_25") (pintype "passive"))
    )
    (net (code "43") (name "/GPIO26") (class "Default")
      (node (ref "J2") (pin "18") (pinfunction "18_18") (pintype "passive"))
      (node (ref "U1") (pin "26") (pinfunction "GPIO26/SPICS1_26") (pintype "passive"))
    )
    (net (code "44") (name "/GPIO33") (class "Default")
      (node (ref "J2") (pin "17") (pinfunction "17_17") (pintype "passive"))
      (node (ref "U1") (pin "28") (pinfunction "GPIO33/SPIIO4/FSPIHD/SUBSPIHD_28") (pintype "passive"))
    )
    (net (code "45") (name "/GPIO34") (class "Default")
      (node (ref "J2") (pin "16") (pinfunction "16_16") (pintype "passive"))
      (node (ref "U1") (pin "29") (pinfunction "GPIO34/SPIIO5/FSPICS0/SUBSPICS0_29") (pintype "passive"))
    )
    (net (code "46") (name "/GPIO35") (class "Default")
      (node (ref "J2") (pin "15") (pinfunction "15_15") (pintype "passive"))
      (node (ref "U1") (pin "31") (pinfunction "GPIO35/SPIIO6/FSPID/SUBSPID_31") (pintype "passive"))
    )
    (net (code "47") (name "/GPIO36") (class "Default")
      (node (ref "J2") (pin "14") (pinfunction "14_14") (pintype "passive"))
      (node (ref "U1") (pin "32") (pinfunction "GPIO36/SPIIO7/FSPICLK/SUBSPICLK_32") (pintype "passive"))
    )
    (net (code "48") (name "/GPIO37") (class "Default")
      (node (ref "J2") (pin "13") (pinfunction "13_13") (pintype "passive"))
      (node (ref "U1") (pin "33") (pinfunction "GPIO37/SPIDQS/FSPIQ/SUBSPIQ_33") (pintype "passive"))
    )
    (net (code "49") (name "/GPIO38") (class "Default")
      (node (ref "J2") (pin "12") (pinfunction "12_12") (pintype "passive"))
      (node (ref "U1") (pin "34") (pinfunction "GPIO38/FSPIWP/SUBSPIWP_34") (pintype "passive"))
    )
    (net (code "50") (name "/GPIO39") (class "Default")
      (node (ref "J2") (pin "11") (pinfunction "11_11") (pintype "passive"))
      (node (ref "U1") (pin "35") (pinfunction "MTCK/GPIO39/CLK_OUT3/SUBSPICS1_35") (pintype "passive"))
    )
    (net (code "51") (name "/GPIO40") (class "Default")
      (node (ref "J2") (pin "10") (pinfunction "10_10") (pintype "passive"))
      (node (ref "U1") (pin "36") (pinfunction "MTDO/GPIO40/CLK_OUT2_36") (pintype "passive"))
    )
    (net (code "52") (name "/GPIO41") (class "Default")
      (node (ref "J2") (pin "9") (pinfunction "9_9") (pintype "passive"))
      (node (ref "U1") (pin "37") (pinfunction "MTDI/GPIO41/CLK_OUT1_37") (pintype "passive"))
    )
    (net (code "53") (name "/GPIO42") (class "Default")
      (node (ref "J2") (pin "8") (pinfunction "8_8") (pintype "passive"))
      (node (ref "U1") (pin "38") (pinfunction "MTMS/GPIO42_38") (pintype "passive"))
    )
    (net (code "54") (name "/GPIO45") (class "Default")
      (node (ref "J2") (pin "5") (pinfunction "5_5") (pintype "passive"))
      (node (ref "U1") (pin "41") (pinfunction "GPIO45_41") (pintype "passive"))
    )
    (net (code "55") (name "/GPIO46") (class "Default")
      (node (ref "J2") (pin "4") (pinfunction "4_4") (pintype "passive"))
      (node (ref "U1") (pin "44") (pinfunction "GPIO46_44") (pintype "passive"))
    )
    (net (code "56") (name "/GPIO47") (class "Default")
      (node (ref "J2") (pin "23") (pinfunction "23_23") (pintype "passive"))
      (node (ref "U1") (pin "27") (pinfunction "GPIO47/SPICLK_P_DIFF/SUBSPICLK_P_DIFF_27") (pintype "passive"))
    )
    (net (code "57") (name "/GPIO48") (class "Default")
      (node (ref "J2") (pin "22") (pinfunction "22_22") (pintype "passive"))
      (node (ref "U1") (pin "30") (pinfunction "GPIO48/SPICLK_N_DIFF/SUBSPICLK_N_DIFF_30") (pintype "passive"))
    )
    (net (code "58") (name "/RTS_FTDI") (class "Default")
      (node (ref "Q1") (pin "2") (pinfunction "E_2") (pintype "passive"))
      (node (ref "R18") (pin "2") (pinfunction "2_2") (pintype "passive"))
      (node (ref "U2") (pin "19") (pinfunction "~{RTS}_19") (pintype "passive"))
    )
    (net (code "59") (name "/RXD_FTDI") (class "Default")
      (node (ref "R21") (pin "2") (pinfunction "2_2") (pintype "passive"))
      (node (ref "U2") (pin "1") (pinfunction "RXD_1") (pintype "passive"))
    )
    (net (code "60") (name "/TXD_FTDI") (class "Default")
      (node (ref "R22") (pin "2") (pinfunction "2_2") (pintype "passive"))
      (node (ref "U2") (pin "17") (pinfunction "TXD_17") (pintype "passive"))
    )
    (net (code "61") (name "/U0RXD") (class "Default")
      (node (ref "J2") (pin "6") (pinfunction "6_6") (pintype "passive"))
      (node (ref "R22") (pin "1") (pinfunction "1_1") (pintype "passive"))
      (node (ref "U1") (pin "40") (pinfunction "U0RXD/GPIO44/CLK_OUT2_40") (pintype "passive"))
    )
    (net (code "62") (name "/U0TXD") (class "Default")
      (node (ref "J2") (pin "7") (pinfunction "7_7") (pintype "passive"))
      (node (ref "R21") (pin "1") (pinfunction "1_1") (pintype "passive"))
      (node (ref "U1") (pin "39") (pinfunction "U0TXD/GPIO43/CLK_OUT1_39") (pintype "passive"))
    )
    (net (code "63") (name "/VBUS_SENSE") (class "Default")
      (node (ref "R11") (pin "2") (pinfunction "2_2") (pintype "passive"))
      (node (ref "R8") (pin "1") (pinfunction "1_1") (pintype "passive"))
      (node (ref "U2") (pin "16") (pinfunction "CBUS3_16") (pintype "passive"))
    )
    (net (code "64") (name "GND") (class "Default")
      (node (ref "C1") (pin "1") (pinfunction "1_1") (pintype "passive"))
      (node (ref "C10") (pin "1") (pinfunction "1_1") (pintype "passive"))
      (node (ref "C11") (pin "1") (pinfunction "1_1") (pintype "passive"))
      (node (ref "C12") (pin "1") (pinfunction "1_1") (pintype "passive"))
      (node (ref "C13") (pin "1") (pinfunction "1_1") (pintype "passive"))
      (node (ref "C14") (pin "1") (pinfunction "1_1") (pintype "passive"))
      (node (ref "C15") (pin "1") (pinfunction "1_1") (pintype "passive"))
      (node (ref "C16") (pin "1") (pinfunction "1_1") (pintype "passive"))
      (node (ref "C17") (pin "1") (pinfunction "1_1") (pintype "passive"))
      (node (ref "C2") (pin "1") (pinfunction "1_1") (pintype "passive"))
      (node (ref "C3") (pin "1") (pinfunction "1_1") (pintype "passive"))
      (node (ref "C4") (pin "1") (pinfunction "1_1") (pintype "passive"))
      (node (ref "C5") (pin "1") (pinfunction "1_1") (pintype "passive"))
      (node (ref "C6") (pin "1") (pinfunction "1_1") (pintype "passive"))
      (node (ref "C7") (pin "1") (pinfunction "1_1") (pintype "passive"))
      (node (ref "C8") (pin "1") (pinfunction "1_1") (pintype "passive"))
      (node (ref "C9") (pin "1") (pinfunction "1_1") (pintype "passive"))
      (node (ref "D1") (pin "1") (pinfunction "1_1") (pintype "passive"))
      (node (ref "D2") (pin "1") (pinfunction "1_1") (pintype "passive"))
      (node (ref "D3") (pin "1") (pinfunction "1_1") (pintype "passive"))
      (node (ref "D4") (pin "1") (pinfunction "1_1") (pintype "passive"))
      (node (ref "D5") (pin "1") (pinfunction "1_1") (pintype "passive"))
      (node (ref "D6") (pin "1") (pinfunction "1_1") (pintype "passive"))
      (node (ref "D7") (pin "1") (pinfunction "1_1") (pintype "passive"))
      (node (ref "J1") (pin "1") (pinfunction "1_1") (pintype "passive"))
      (node (ref "J1") (pin "23") (pinfunction "23_23") (pintype "passive"))
      (node (ref "J2") (pin "2") (pinfunction "2_2") (pintype "passive"))
      (node (ref "J2") (pin "24") (pinfunction "24_24") (pintype "passive"))
      (node (ref "J3") (pin "A1B12") (pinfunction "GND_A1B12_A1B12") (pintype "passive"))
      (node (ref "J3") (pin "B1A12") (pinfunction "GND_B1A12_B1A12") (pintype "passive"))
      (node (ref "J3") (pin "S1") (pinfunction "SHIELD_1_S1") (pintype "passive"))
      (node (ref "J3") (pin "S2") (pinfunction "SHIELD_2_S2") (pintype "passive"))
      (node (ref "J3") (pin "S3") (pinfunction "SHIELD_3_S3") (pintype "passive"))
      (node (ref "J3") (pin "S4") (pinfunction "SHIELD_4_S4") (pintype "passive"))
      (node (ref "J4") (pin "A1B12") (pinfunction "GND_A1B12_A1B12") (pintype "passive"))
      (node (ref "J4") (pin "B1A12") (pinfunction "GND_B1A12_B1A12") (pintype "passive"))
      (node (ref "J4") (pin "S1") (pinfunction "SHIELD_1_S1") (pintype "passive"))
      (node (ref "J4") (pin "S2") (pinfunction "SHIELD_2_S2") (pintype "passive"))
      (node (ref "J4") (pin "S3") (pinfunction "SHIELD_3_S3") (pintype "passive"))
      (node (ref "J4") (pin "S4") (pinfunction "SHIELD_4_S4") (pintype "passive"))
      (node (ref "R10") (pin "1") (pinfunction "1_1") (pintype "passive"))
      (node (ref "R11") (pin "1") (pinfunction "1_1") (pintype "passive"))
      (node (ref "R13") (pin "1") (pinfunction "1_1") (pintype "passive"))
      (node (ref "R14") (pin "1") (pinfunction "1_1") (pintype "passive"))
      (node (ref "R7") (pin "1") (pinfunction "1_1") (pintype "passive"))
      (node (ref "R9") (pin "1") (pinfunction "1_1") (pintype "passive"))
      (node (ref "SW1") (pin "3") (pinfunction "3_3") (pintype "passive"))
      (node (ref "SW1") (pin "4") (pinfunction "4_4") (pintype "passive"))
      (node (ref "SW2") (pin "3") (pinfunction "3_3") (pintype "passive"))
      (node (ref "SW2") (pin "4") (pinfunction "4_4") (pintype "passive"))
      (node (ref "U1") (pin "1") (pinfunction "GND_01_1") (pintype "passive"))
      (node (ref "U1") (pin "2") (pinfunction "GND_02_2") (pintype "passive"))
      (node (ref "U1") (pin "42") (pinfunction "GND_42") (pintype "passive"))
      (node (ref "U1") (pin "43") (pinfunction "GND_43") (pintype "passive"))
      (node (ref "U1") (pin "46") (pinfunction "GND_46_46") (pintype "passive"))
      (node (ref "U1") (pin "47") (pinfunction "GND_47_47") (pintype "passive"))
      (node (ref "U1") (pin "48") (pinfunction "GND_48_48") (pintype "passive"))
      (node (ref "U1") (pin "49") (pinfunction "GND_49_49") (pintype "passive"))
      (node (ref "U1") (pin "50") (pinfunction "GND_50_50") (pintype "passive"))
      (node (ref "U1") (pin "51") (pinfunction "GND_51_51") (pintype "passive"))
      (node (ref "U1") (pin "52") (pinfunction "GND_52_52") (pintype "passive"))
      (node (ref "U1") (pin "53") (pinfunction "GND_53_53") (pintype "passive"))
      (node (ref "U1") (pin "54") (pinfunction "GND_54_54") (pintype "passive"))
      (node (ref "U1") (pin "55") (pinfunction "GND_55_55") (pintype "passive"))
      (node (ref "U1") (pin "56") (pinfunction "GND_56_56") (pintype "passive"))
      (node (ref "U1") (pin "57") (pinfunction "GND_57_57") (pintype "passive"))
      (node (ref "U1") (pin "58") (pinfunction "GND_58_58") (pintype "passive"))
      (node (ref "U1") (pin "59") (pinfunction "GND_59_59") (pintype "passive"))
      (node (ref "U1") (pin "60") (pinfunction "GND_60_60") (pintype "passive"))
      (node (ref "U1") (pin "61") (pinfunction "GND_61_61") (pintype "passive"))
      (node (ref "U1") (pin "62") (pinfunction "GND_62_62") (pintype "passive"))
      (node (ref "U1") (pin "63") (pinfunction "GND_63_63") (pintype "passive"))
      (node (ref "U1") (pin "64") (pinfunction "GND_64_64") (pintype "passive"))
      (node (ref "U1") (pin "65") (pinfunction "GND_65_65") (pintype "passive"))
      (node (ref "U1") (pin "66") (pinfunction "GND_66_66") (pintype "passive"))
      (node (ref "U1") (pin "67") (pinfunction "GND_67_67") (pintype "passive"))
      (node (ref "U1") (pin "68") (pinfunction "GND_68_68") (pintype "passive"))
      (node (ref "U1") (pin "69") (pinfunction "GND_69_69") (pintype "passive"))
      (node (ref "U1") (pin "70") (pinfunction "GND_70_70") (pintype "passive"))
      (node (ref "U1") (pin "71") (pinfunction "GND_71_71") (pintype "passive"))
      (node (ref "U1") (pin "72") (pinfunction "GND_72_72") (pintype "passive"))
      (node (ref "U1") (pin "73") (pinfunction "GND_73_73") (pintype "passive"))
      (node (ref "U2") (pin "13") (pinfunction "GND_13") (pintype "passive"))
      (node (ref "U2") (pin "21") (pinfunction "GND_21") (pintype "passive"))
      (node (ref "U2") (pin "3") (pinfunction "GND_3") (pintype "passive"))
      (node (ref "U3") (pin "2") (pinfunction "GND_2") (pintype "power_in"))
      (node (ref "U3") (pin "4") (pinfunction "GND_4") (pintype "power_in"))
    )
    (net (code "65") (name "Net-(D4-Pad2)") (class "Default")
      (node (ref "D4") (pin "2") (pinfunction "2_2") (pintype "passive"))
      (node (ref "R12") (pin "1") (pinfunction "1_1") (pintype "passive"))
    )
    (net (code "66") (name "Net-(D8-Pad2)") (class "Default")
      (node (ref "D8") (pin "2") (pinfunction "2_2") (pintype "passive"))
      (node (ref "R15") (pin "1") (pinfunction "1_1") (pintype "passive"))
    )
    (net (code "67") (name "Net-(J3-CC1)") (class "Default")
      (node (ref "J3") (pin "A5") (pinfunction "CC1_A5") (pintype "passive"))
      (node (ref "R10") (pin "2") (pinfunction "2_2") (pintype "passive"))
    )
    (net (code "68") (name "Net-(J3-CC2)") (class "Default")
      (node (ref "J3") (pin "B5") (pinfunction "CC2_B5") (pintype "passive"))
      (node (ref "R9") (pin "2") (pinfunction "2_2") (pintype "passive"))
    )
    (net (code "69") (name "Net-(J4-CC1)") (class "Default")
      (node (ref "J4") (pin "A5") (pinfunction "CC1_A5") (pintype "passive"))
      (node (ref "R14") (pin "2") (pinfunction "2_2") (pintype "passive"))
    )
    (net (code "70") (name "Net-(J4-CC2)") (class "Default")
      (node (ref "J4") (pin "B5") (pinfunction "CC2_B5") (pintype "passive"))
      (node (ref "R13") (pin "2") (pinfunction "2_2") (pintype "passive"))
    )
    (net (code "71") (name "Net-(Q1-B)") (class "Default")
      (node (ref "Q1") (pin "1") (pinfunction "B_1") (pintype "passive"))
      (node (ref "R16") (pin "1") (pinfunction "1_1") (pintype "passive"))
    )
    (net (code "72") (name "Net-(Q2-B)") (class "Default")
      (node (ref "Q2") (pin "1") (pinfunction "B_1") (pintype "passive"))
      (node (ref "R18") (pin "1") (pinfunction "1_1") (pintype "passive"))
    )
    (net (code "73") (name "Net-(U2-CBUS0)") (class "Default")
      (node (ref "R7") (pin "2") (pinfunction "2_2") (pintype "passive"))
      (node (ref "U2") (pin "15") (pinfunction "CBUS0_15") (pintype "passive"))
    )
    (net (code "74") (name "unconnected-(J1-Pad24)") (class "Default")
      (node (ref "J1") (pin "24") (pinfunction "24_24") (pintype "passive+no_connect"))
    )
    (net (code "75") (name "unconnected-(J3-SBU1-PadA8)") (class "Default")
      (node (ref "J3") (pin "A8") (pinfunction "SBU1_A8") (pintype "passive+no_connect"))
    )
    (net (code "76") (name "unconnected-(J3-SBU2-PadB8)") (class "Default")
      (node (ref "J3") (pin "B8") (pinfunction "SBU2_B8") (pintype "passive+no_connect"))
    )
    (net (code "77") (name "unconnected-(J4-SBU1-PadA8)") (class "Default")
      (node (ref "J4") (pin "A8") (pinfunction "SBU1_A8") (pintype "passive+no_connect"))
    )
    (net (code "78") (name "unconnected-(J4-SBU2-PadB8)") (class "Default")
      (node (ref "J4") (pin "B8") (pinfunction "SBU2_B8") (pintype "passive+no_connect"))
    )
    (net (code "79") (name "unconnected-(U2-CBUS1-Pad14)") (class "Default")
      (node (ref "U2") (pin "14") (pinfunction "CBUS1_14") (pintype "passive+no_connect"))
    )
    (net (code "80") (name "unconnected-(U2-CBUS2-Pad7)") (class "Default")
      (node (ref "U2") (pin "7") (pinfunction "CBUS2_7") (pintype "passive+no_connect"))
    )
    (net (code "81") (name "unconnected-(U2-~{CTS}-Pad6)") (class "Default")
      (node (ref "U2") (pin "6") (pinfunction "~{CTS}_6") (pintype "passive+no_connect"))
    )
    (net (code "82") (name "unconnected-(U2-~{DCD}-Pad5)") (class "Default")
      (node (ref "U2") (pin "5") (pinfunction "~{DCD}_5") (pintype "passive+no_connect"))
    )
    (net (code "83") (name "unconnected-(U2-~{DSR}-Pad4)") (class "Default")
      (node (ref "U2") (pin "4") (pinfunction "~{DSR}_4") (pintype "passive+no_connect"))
    )
    (net (code "84") (name "unconnected-(U2-~{RI}-Pad2)") (class "Default")
      (node (ref "U2") (pin "2") (pinfunction "~{RI}_2") (pintype "passive+no_connect"))
    )
  )
)
